# NDIR_SensorInterface.net
KiCad netlist of a schematic drawn in EAGLE
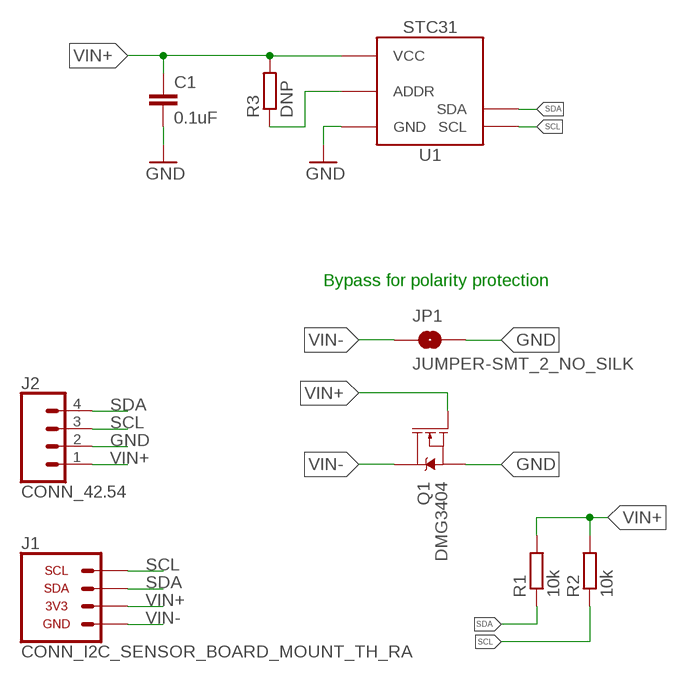
[diagram p0: schematic, sheet 1]

(export (version "E")
  (design (tool "Eeschema 10.0.6"))
  (components
    (comp (ref "C1")
      (value "0.1uF")
      (footprint "eagle-import:C0603")
      (fields (field (name "MF") "Murata") (field (name "MPN") "GCM188R71E104KA57D"))
      (libsource (lib "eagle-import") (part "C-EUC06030.1UF"))
    )
    (comp (ref "J1")
      (value "CONN_I2C_SENSOR_BOARD_MOUNT_TH_RA")
      (footprint "eagle-import:CONEC_43-01204")
      (fields (field (name "MF") "Conec") (field (name "MPN") "43-01204"))
      (libsource (lib "eagle-import") (part "CONN_I2C_SENSOR_BOARD_MOUNT_TH_RA"))
    )
    (comp (ref "J2")
      (value "CONN_42.54")
      (footprint "eagle-import:1X04")
      (fields (field (name "MF") "Mill-Max") (field (name "MPN") "800-10-004-10-002000"))
      (libsource (lib "eagle-import") (part "CONN_42.54"))
    )
    (comp (ref "JP1")
      (value "JUMPER-SMT_2_NO_SILK")
      (footprint "eagle-import:SMT-JUMPER_2_NO_SILK")
      (libsource (lib "eagle-import") (part "JUMPER-SMT_2_NO_SILK"))
    )
    (comp (ref "Q1")
      (value "DMG3404")
      (footprint "eagle-import:SOT23-3")
      (fields (field (name "MF") "Diodes Incorporated") (field (name "MPN") "DMG3404L-7"))
      (libsource (lib "eagle-import") (part "MOSFET-NCH-DMG3404L"))
    )
    (comp (ref "R1")
      (value "10k")
      (footprint "eagle-import:R0603")
      (fields (field (name "MF") "Yageo") (field (name "MPN") "RC0603FR-0710KL"))
      (libsource (lib "eagle-import") (part "R-EU_R060310K"))
    )
    (comp (ref "R2")
      (value "10k")
      (footprint "eagle-import:R0603")
      (fields (field (name "MF") "Yageo") (field (name "MPN") "RC0603FR-0710KL"))
      (libsource (lib "eagle-import") (part "R-EU_R060310K"))
    )
    (comp (ref "R3")
      (value "DNP")
      (footprint "eagle-import:R0603")
      (fields (field (name "MF") "Yageo"))
      (libsource (lib "eagle-import") (part "R-EU_R0603"))
    )
    (comp (ref "U1")
      (value "STC31")
      (footprint "eagle-import:STC31")
      (fields (field (name "DISP") "STC31") (field (name "MF") "Sensirion") (field (name "MPN") "STC31-C-R3"))
      (libsource (lib "eagle-import") (part "STC31"))
    )
  )
  (nets
    (net (code "1") (name "GND") (class "Default")
      (node (ref "C1") (pin "2") (pinfunction "2_2") (pintype "passive"))
      (node (ref "J2") (pin "2") (pinfunction "2_2") (pintype "passive"))
      (node (ref "JP1") (pin "2") (pinfunction "2_2") (pintype "passive"))
      (node (ref "Q1") (pin "2") (pinfunction "S_2") (pintype "bidirectional"))
      (node (ref "U1") (pin "1") (pinfunction "GND_1") (pintype "power_in"))
      (node (ref "U1") (pin "11") (pinfunction "GND_11") (pintype "power_in"))
      (node (ref "U1") (pin "5") (pinfunction "GND_5") (pintype "power_in"))
      (node (ref "U1") (pin "9") (pinfunction "GND_9") (pintype "power_in"))
      (node (ref "U1") (pin "EP") (pinfunction "GND_EP") (pintype "power_in"))
    )
    (net (code "2") (name "Net-(U1-ADDR)") (class "Default")
      (node (ref "R3") (pin "1") (pinfunction "1_1") (pintype "passive"))
      (node (ref "U1") (pin "3") (pinfunction "ADDR_3") (pintype "input"))
    )
    (net (code "3") (name "SCL") (class "Default")
      (node (ref "J1") (pin "3") (pinfunction "SCL_3") (pintype "passive"))
      (node (ref "J2") (pin "3") (pinfunction "3_3") (pintype "passive"))
      (node (ref "R2") (pin "1") (pinfunction "1_1") (pintype "passive"))
      (node (ref "U1") (pin "4") (pinfunction "SCL_4") (pintype "input"))
    )
    (net (code "4") (name "SDA") (class "Default")
      (node (ref "J1") (pin "1") (pinfunction "SDA_1") (pintype "passive"))
      (node (ref "J2") (pin "4") (pinfunction "4_4") (pintype "passive"))
      (node (ref "R1") (pin "1") (pinfunction "1_1") (pintype "passive"))
      (node (ref "U1") (pin "7") (pinfunction "SDA_7") (pintype "bidirectional"))
    )
    (net (code "5") (name "VIN+") (class "Default")
      (node (ref "C1") (pin "1") (pinfunction "1_1") (pintype "passive"))
      (node (ref "J1") (pin "2") (pinfunction "3V3_2") (pintype "passive"))
      (node (ref "J2") (pin "1") (pinfunction "1_1") (pintype "passive"))
      (node (ref "Q1") (pin "1") (pinfunction "G_1") (pintype "bidirectional"))
      (node (ref "R1") (pin "2") (pinfunction "2_2") (pintype "passive"))
      (node (ref "R2") (pin "2") (pinfunction "2_2") (pintype "passive"))
      (node (ref "R3") (pin "2") (pinfunction "2_2") (pintype "passive"))
      (node (ref "U1") (pin "6") (pinfunction "VCC_6") (pintype "power_in"))
    )
    (net (code "6") (name "VIN-") (class "Default")
      (node (ref "J1") (pin "4") (pinfunction "GND_4") (pintype "passive"))
      (node (ref "JP1") (pin "1") (pinfunction "1_1") (pintype "passive"))
      (node (ref "Q1") (pin "3") (pinfunction "D_3") (pintype "bidirectional"))
    )
  )
)
